# schematic.net
KiCad netlist of a schematic drawn in EasyEDA
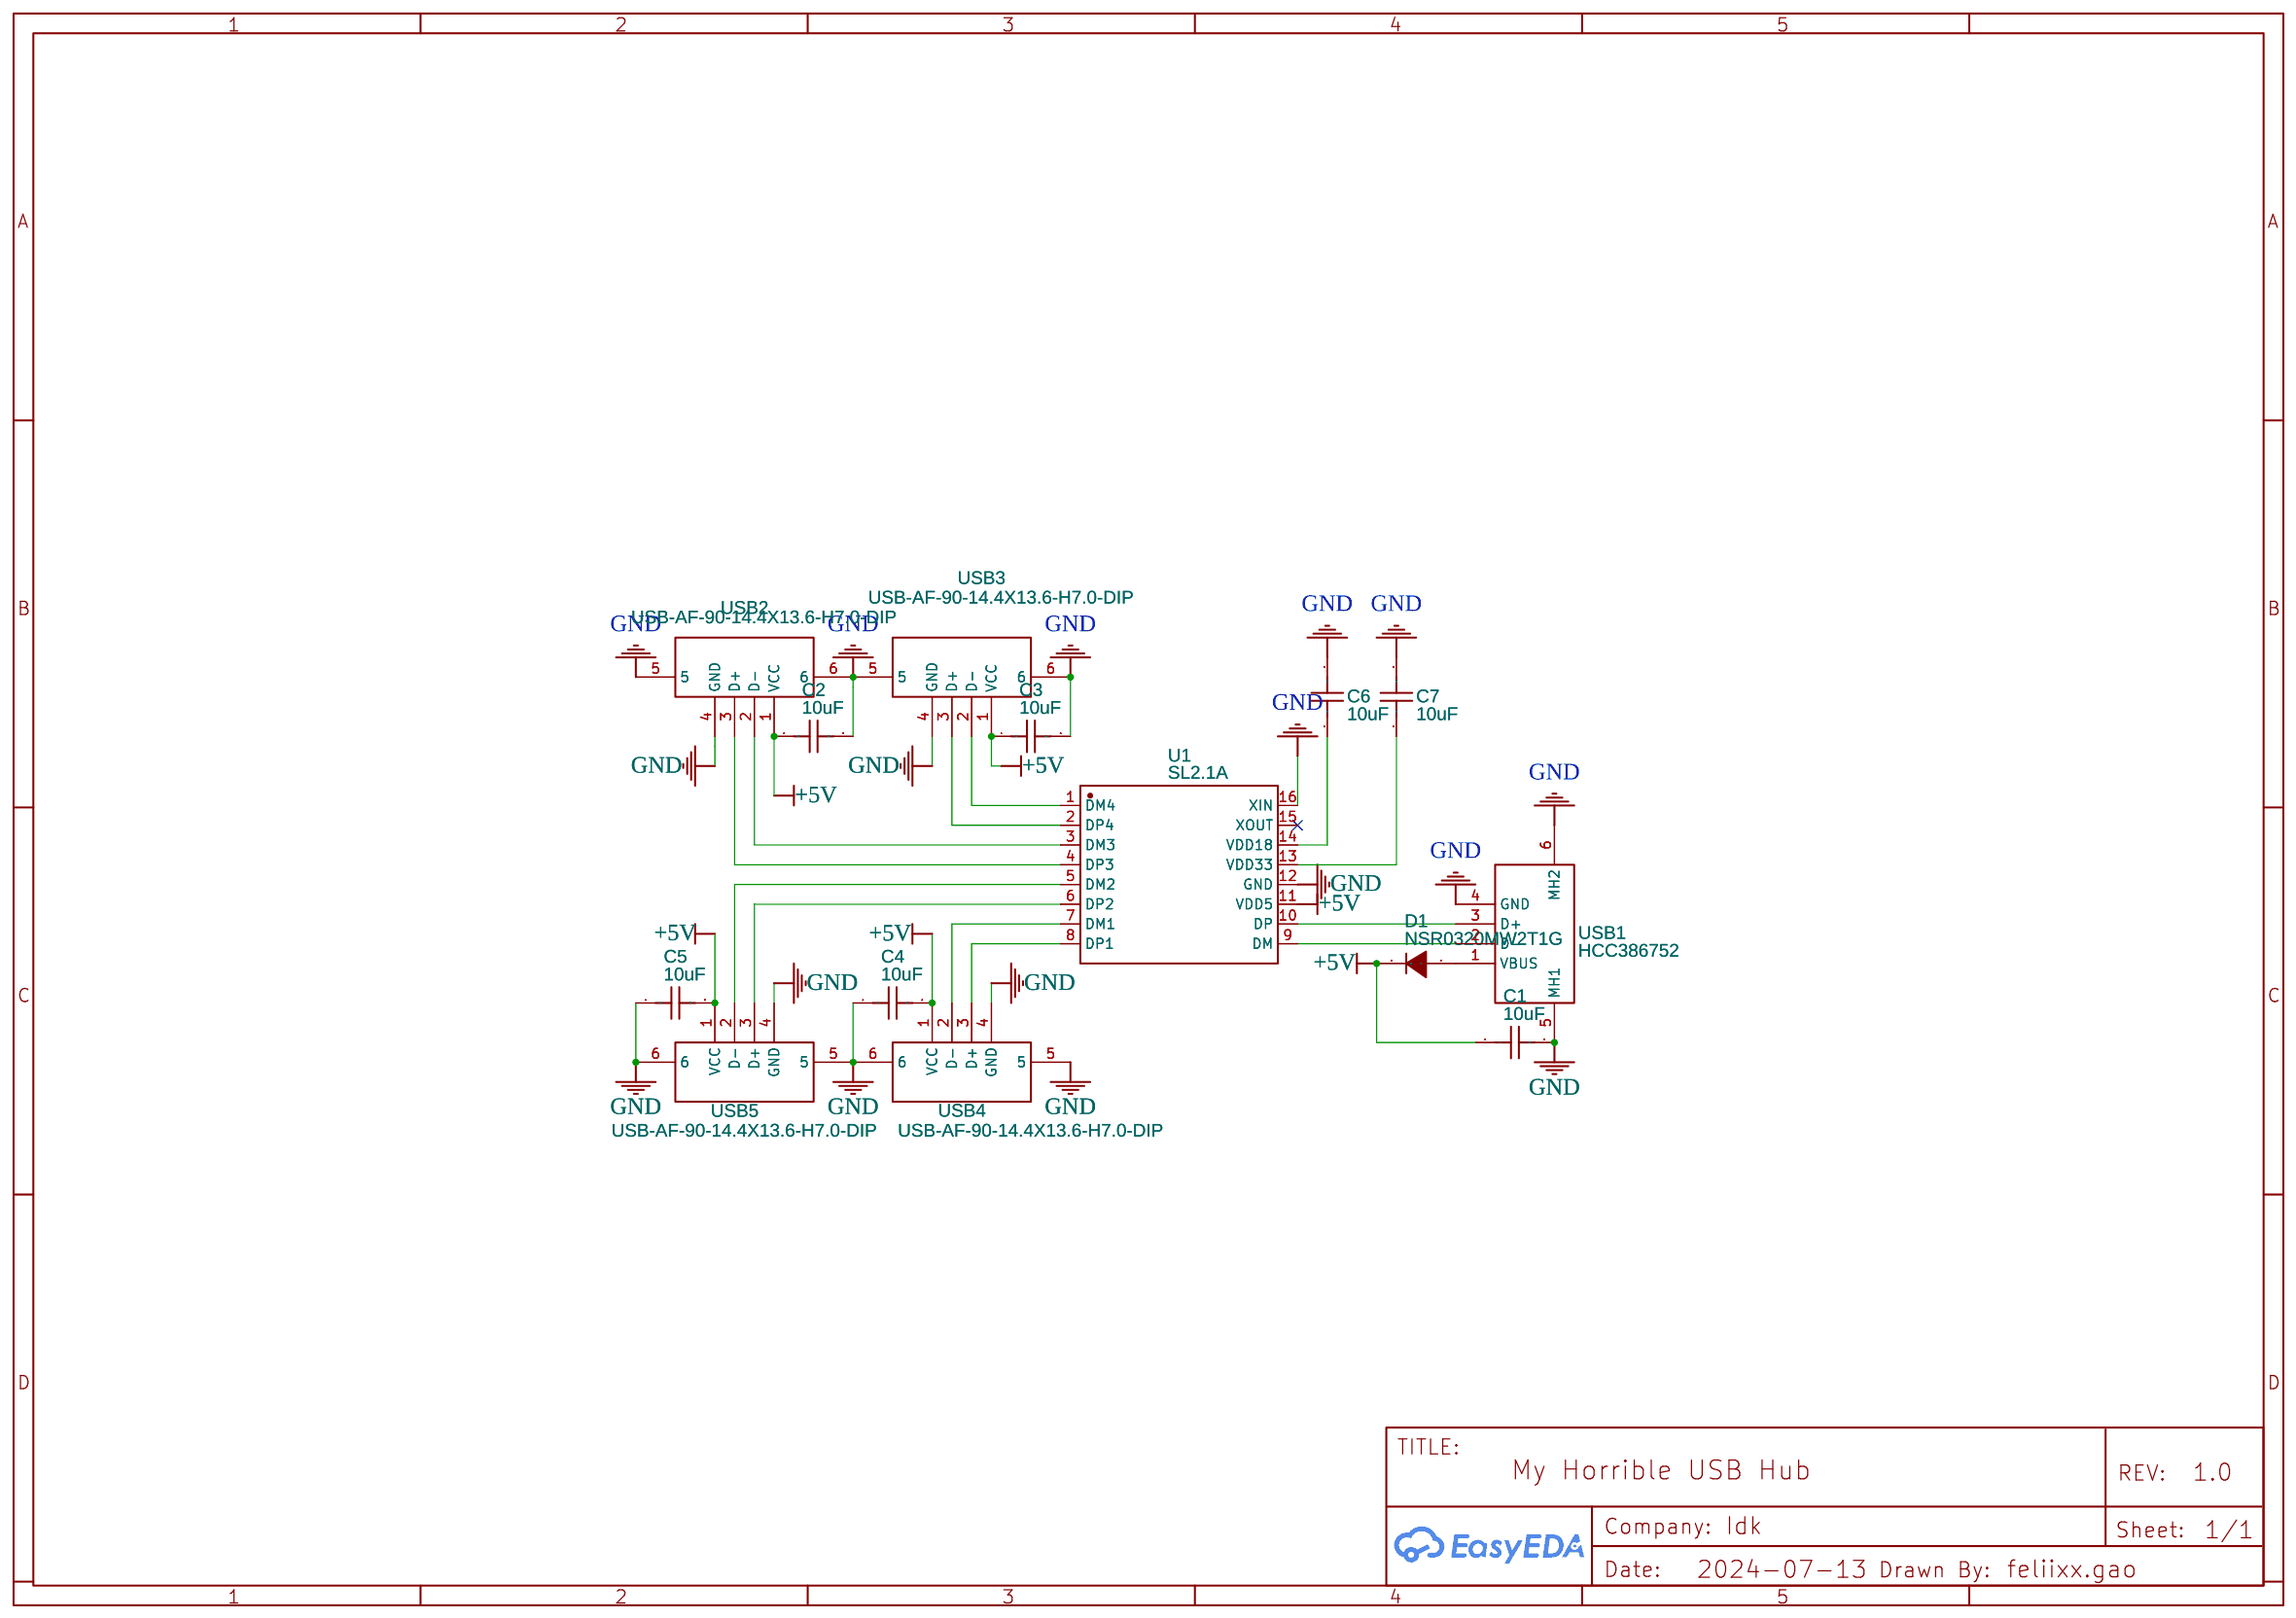
[diagram p0: schematic sheet]

(export (version "E")
  (design (tool "Eeschema 10.0.6"))
  (components
    (comp (ref "C1")
      (value "10uF")
      (fields
        (field (name "Manufacturer Part") "CL10A106KP8NNNC")
        (field (name "Manufacturer") "SAMSUNG(三星)")
      )
      (libsource (lib "") (part "CL10A106KP8NNNC"))
    )
    (comp (ref "C2")
      (value "10uF")
      (fields
        (field (name "Manufacturer Part") "CL10A106KP8NNNC")
        (field (name "Manufacturer") "SAMSUNG(三星)")
      )
      (libsource (lib "") (part "CL10A106KP8NNNC"))
    )
    (comp (ref "C3")
      (value "10uF")
      (fields
        (field (name "Manufacturer Part") "CL10A106KP8NNNC")
        (field (name "Manufacturer") "SAMSUNG(三星)")
      )
      (libsource (lib "") (part "CL10A106KP8NNNC"))
    )
    (comp (ref "C4")
      (value "10uF")
      (fields
        (field (name "Manufacturer Part") "CL10A106KP8NNNC")
        (field (name "Manufacturer") "SAMSUNG(三星)")
      )
      (libsource (lib "") (part "CL10A106KP8NNNC"))
    )
    (comp (ref "C5")
      (value "10uF")
      (fields
        (field (name "Manufacturer Part") "CL10A106KP8NNNC")
        (field (name "Manufacturer") "SAMSUNG(三星)")
      )
      (libsource (lib "") (part "CL10A106KP8NNNC"))
    )
    (comp (ref "C6")
      (value "10uF")
      (fields
        (field (name "Manufacturer Part") "CL10A106KP8NNNC")
        (field (name "Manufacturer") "SAMSUNG(三星)")
      )
      (libsource (lib "") (part "CL10A106KP8NNNC_1"))
    )
    (comp (ref "C7")
      (value "10uF")
      (fields
        (field (name "Manufacturer Part") "CL10A106KP8NNNC")
        (field (name "Manufacturer") "SAMSUNG(三星)")
      )
      (libsource (lib "") (part "CL10A106KP8NNNC_1"))
    )
    (comp (ref "D1")
      (value "NSR0320MW2T1G")
      (fields (field (name "Manufacturer") "onsemi(安森美)"))
      (libsource (lib "") (part "NSR0320MW2T1G"))
    )
    (comp (ref "U1")
      (value "SL2.1A")
      (fields (field (name "Manufacturer") "CoreChips(和芯润德)"))
      (libsource (lib "") (part "SL2.1A"))
    )
    (comp (ref "USB1")
      (value "HCC386752")
      (fields (field (name "Manufacturer Part") "U-USBAR04P-M003") (field (name "Manufacturer") "Ckmtw(灿科盟)"))
      (libsource (lib "") (part "HCC386752"))
    )
    (comp (ref "USB2")
      (value "USB-AF-90-14.4X13.6-H7.0-DIP")
      (fields (field (name "Manufacturer Part") "903-131A1011D10100") (field (name "Manufacturer") "精拓金"))
      (libsource (lib "") (part "USB-AF-90-14.4X13.6-H7.0-DIP"))
    )
    (comp (ref "USB3")
      (value "USB-AF-90-14.4X13.6-H7.0-DIP")
      (fields (field (name "Manufacturer Part") "903-131A1011D10100") (field (name "Manufacturer") "精拓金"))
      (libsource (lib "") (part "USB-AF-90-14.4X13.6-H7.0-DIP"))
    )
    (comp (ref "USB4")
      (value "USB-AF-90-14.4X13.6-H7.0-DIP")
      (fields (field (name "Manufacturer Part") "903-131A1011D10100") (field (name "Manufacturer") "精拓金"))
      (libsource (lib "") (part "USB-AF-90-14.4X13.6-H7.0-DIP_1"))
    )
    (comp (ref "USB5")
      (value "USB-AF-90-14.4X13.6-H7.0-DIP")
      (fields (field (name "Manufacturer Part") "903-131A1011D10100") (field (name "Manufacturer") "精拓金"))
      (libsource (lib "") (part "USB-AF-90-14.4X13.6-H7.0-DIP_1"))
    )
  )
  (nets
    (net (code "1") (name "+5V") (class "Default")
      (node (ref "C1") (pin "1") (pinfunction "1_1") (pintype "unspecified"))
      (node (ref "C2") (pin "1") (pinfunction "1_1") (pintype "unspecified"))
      (node (ref "C3") (pin "1") (pinfunction "1_1") (pintype "unspecified"))
      (node (ref "C4") (pin "2") (pinfunction "2_2") (pintype "unspecified"))
      (node (ref "C5") (pin "2") (pinfunction "2_2") (pintype "unspecified"))
      (node (ref "D1") (pin "1") (pinfunction "C_1") (pintype "unspecified"))
      (node (ref "U1") (pin "11") (pinfunction "VDD5_11") (pintype "unspecified"))
      (node (ref "USB2") (pin "1") (pinfunction "VCC_1") (pintype "unspecified"))
      (node (ref "USB3") (pin "1") (pinfunction "VCC_1") (pintype "unspecified"))
      (node (ref "USB4") (pin "1") (pinfunction "VCC_1") (pintype "unspecified"))
      (node (ref "USB5") (pin "1") (pinfunction "VCC_1") (pintype "unspecified"))
    )
    (net (code "2") (name "GND") (class "Default")
      (node (ref "C1") (pin "2") (pinfunction "2_2") (pintype "unspecified"))
      (node (ref "C2") (pin "2") (pinfunction "2_2") (pintype "unspecified"))
      (node (ref "C3") (pin "2") (pinfunction "2_2") (pintype "unspecified"))
      (node (ref "C4") (pin "1") (pinfunction "1_1") (pintype "unspecified"))
      (node (ref "C5") (pin "1") (pinfunction "1_1") (pintype "unspecified"))
      (node (ref "C6") (pin "2") (pinfunction "2_2") (pintype "unspecified"))
      (node (ref "C7") (pin "2") (pinfunction "2_2") (pintype "unspecified"))
      (node (ref "U1") (pin "12") (pinfunction "GND_12") (pintype "unspecified"))
      (node (ref "U1") (pin "16") (pinfunction "XIN_16") (pintype "unspecified"))
      (node (ref "USB1") (pin "4") (pinfunction "GND_4") (pintype "unspecified"))
      (node (ref "USB1") (pin "5") (pinfunction "MH1_5") (pintype "unspecified"))
      (node (ref "USB1") (pin "6") (pinfunction "MH2_6") (pintype "unspecified"))
      (node (ref "USB2") (pin "4") (pinfunction "GND_4") (pintype "unspecified"))
      (node (ref "USB2") (pin "5") (pinfunction "5_5") (pintype "unspecified"))
      (node (ref "USB2") (pin "6") (pinfunction "6_6") (pintype "unspecified"))
      (node (ref "USB3") (pin "4") (pinfunction "GND_4") (pintype "unspecified"))
      (node (ref "USB3") (pin "5") (pinfunction "5_5") (pintype "unspecified"))
      (node (ref "USB3") (pin "6") (pinfunction "6_6") (pintype "unspecified"))
      (node (ref "USB4") (pin "4") (pinfunction "GND_4") (pintype "unspecified"))
      (node (ref "USB4") (pin "5") (pinfunction "5_5") (pintype "unspecified"))
      (node (ref "USB4") (pin "6") (pinfunction "6_6") (pintype "unspecified"))
      (node (ref "USB5") (pin "4") (pinfunction "GND_4") (pintype "unspecified"))
      (node (ref "USB5") (pin "5") (pinfunction "5_5") (pintype "unspecified"))
      (node (ref "USB5") (pin "6") (pinfunction "6_6") (pintype "unspecified"))
    )
    (net (code "3") (name "Net-(D1-A)") (class "Default")
      (node (ref "D1") (pin "2") (pinfunction "A_2") (pintype "unspecified"))
      (node (ref "USB1") (pin "1") (pinfunction "VBUS_1") (pintype "unspecified"))
    )
    (net (code "4") (name "Net-(U1-DM)") (class "Default")
      (node (ref "U1") (pin "9") (pinfunction "DM_9") (pintype "unspecified"))
      (node (ref "USB1") (pin "2") (pinfunction "D-_2") (pintype "unspecified"))
    )
    (net (code "5") (name "Net-(U1-DM1)") (class "Default")
      (node (ref "U1") (pin "7") (pinfunction "DM1_7") (pintype "unspecified"))
      (node (ref "USB4") (pin "2") (pinfunction "D-_2") (pintype "unspecified"))
    )
    (net (code "6") (name "Net-(U1-DM2)") (class "Default")
      (node (ref "U1") (pin "5") (pinfunction "DM2_5") (pintype "unspecified"))
      (node (ref "USB5") (pin "2") (pinfunction "D-_2") (pintype "unspecified"))
    )
    (net (code "7") (name "Net-(U1-DM3)") (class "Default")
      (node (ref "U1") (pin "3") (pinfunction "DM3_3") (pintype "unspecified"))
      (node (ref "USB2") (pin "2") (pinfunction "D-_2") (pintype "unspecified"))
    )
    (net (code "8") (name "Net-(U1-DM4)") (class "Default")
      (node (ref "U1") (pin "1") (pinfunction "DM4_1") (pintype "unspecified"))
      (node (ref "USB3") (pin "2") (pinfunction "D-_2") (pintype "unspecified"))
    )
    (net (code "9") (name "Net-(U1-DP)") (class "Default")
      (node (ref "U1") (pin "10") (pinfunction "DP_10") (pintype "unspecified"))
      (node (ref "USB1") (pin "3") (pinfunction "D+_3") (pintype "unspecified"))
    )
    (net (code "10") (name "Net-(U1-DP1)") (class "Default")
      (node (ref "U1") (pin "8") (pinfunction "DP1_8") (pintype "unspecified"))
      (node (ref "USB4") (pin "3") (pinfunction "D+_3") (pintype "unspecified"))
    )
    (net (code "11") (name "Net-(U1-DP2)") (class "Default")
      (node (ref "U1") (pin "6") (pinfunction "DP2_6") (pintype "unspecified"))
      (node (ref "USB5") (pin "3") (pinfunction "D+_3") (pintype "unspecified"))
    )
    (net (code "12") (name "Net-(U1-DP3)") (class "Default")
      (node (ref "U1") (pin "4") (pinfunction "DP3_4") (pintype "unspecified"))
      (node (ref "USB2") (pin "3") (pinfunction "D+_3") (pintype "unspecified"))
    )
    (net (code "13") (name "Net-(U1-DP4)") (class "Default")
      (node (ref "U1") (pin "2") (pinfunction "DP4_2") (pintype "unspecified"))
      (node (ref "USB3") (pin "3") (pinfunction "D+_3") (pintype "unspecified"))
    )
    (net (code "14") (name "Net-(U1-VDD18)") (class "Default")
      (node (ref "C6") (pin "1") (pinfunction "1_1") (pintype "unspecified"))
      (node (ref "U1") (pin "14") (pinfunction "VDD18_14") (pintype "unspecified"))
    )
    (net (code "15") (name "Net-(U1-VDD33)") (class "Default")
      (node (ref "C7") (pin "1") (pinfunction "1_1") (pintype "unspecified"))
      (node (ref "U1") (pin "13") (pinfunction "VDD33_13") (pintype "unspecified"))
    )
    (net (code "16") (name "unconnected-(U1-XOUT-Pad15)") (class "Default")
      (node (ref "U1") (pin "15") (pinfunction "XOUT_15") (pintype "unspecified+no_connect"))
    )
  )
)
